# Peripheral.net
KiCad netlist of a schematic drawn in Altium Designer
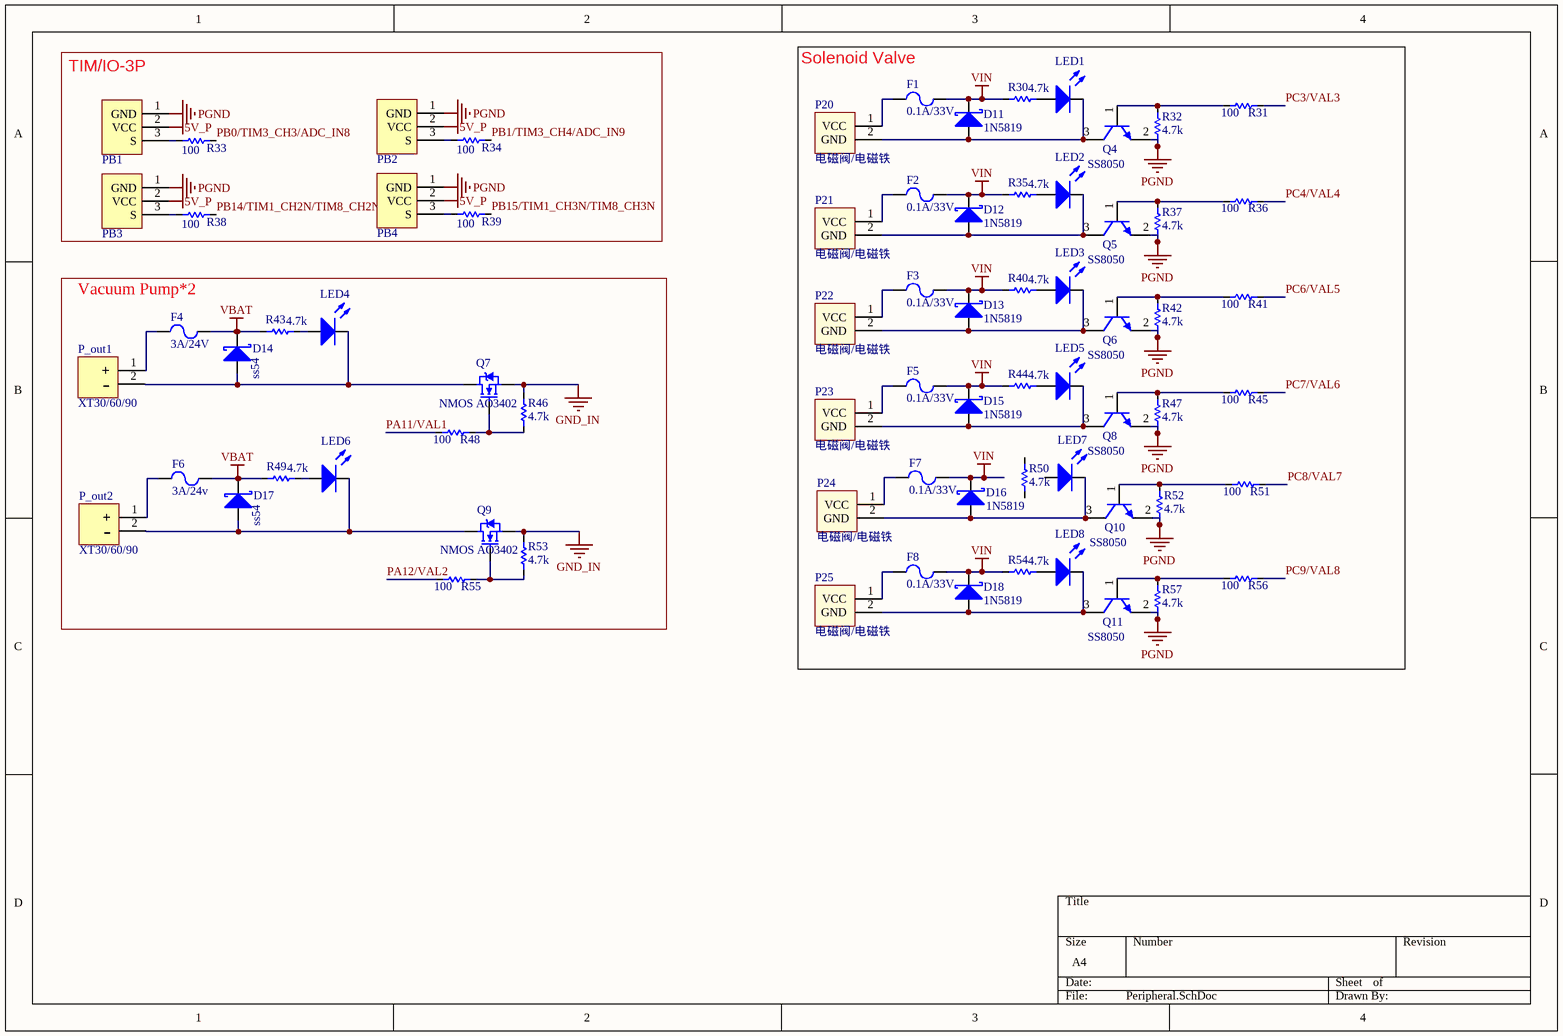
[diagram p0: Peripheral.SchDoc]

(export (version "E")
  (design (tool "Eeschema 10.0.6"))
  (components
    (comp (ref "D11")
      (value "1N5819")
      (footprint "SOD-323-")
      (description "Schottky Diode")
      (fields (field (name "PUBLISHER") "Altium Limited"))
      (libsource (lib "MyComponents_v2.5") (part "D Schottky"))
    )
    (comp (ref "D12")
      (value "1N5819")
      (footprint "SOD-323-")
      (description "Schottky Diode")
      (fields (field (name "PUBLISHER") "Altium Limited"))
      (libsource (lib "MyComponents_v2.5") (part "D Schottky"))
    )
    (comp (ref "D13")
      (value "1N5819")
      (footprint "SOD-323-")
      (description "Schottky Diode")
      (fields (field (name "PUBLISHER") "Altium Limited"))
      (libsource (lib "MyComponents_v2.5") (part "D Schottky"))
    )
    (comp (ref "D14")
      (value "ss54")
      (footprint "SMAF/DO-214AC")
      (description "Schottky Diode")
      (fields (field (name "PUBLISHER") "Altium Limited"))
      (libsource (lib "MyComponents_v2.5") (part "D Schottky_SOD323"))
    )
    (comp (ref "D15")
      (value "1N5819")
      (footprint "SOD-323-")
      (description "Schottky Diode")
      (fields (field (name "PUBLISHER") "Altium Limited"))
      (libsource (lib "MyComponents_v2.5") (part "D Schottky"))
    )
    (comp (ref "D16")
      (value "1N5819")
      (footprint "SOD-323-")
      (description "Schottky Diode")
      (fields (field (name "PUBLISHER") "Altium Limited"))
      (libsource (lib "MyComponents_v2.5") (part "D Schottky"))
    )
    (comp (ref "D17")
      (value "ss54")
      (footprint "SMAF/DO-214AC")
      (description "Schottky Diode")
      (fields (field (name "PUBLISHER") "Altium Limited"))
      (libsource (lib "MyComponents_v2.5") (part "D Schottky_SOD323"))
    )
    (comp (ref "D18")
      (value "1N5819")
      (footprint "SOD-323-")
      (description "Schottky Diode")
      (fields (field (name "PUBLISHER") "Altium Limited"))
      (libsource (lib "MyComponents_v2.5") (part "D Schottky"))
    )
    (comp (ref "F1")
      (value "0.1A/33V")
      (footprint "0603C")
      (description "0603自恢复保险丝")
      (libsource (lib "MyComponents_v2.5") (part "Finance"))
    )
    (comp (ref "F2")
      (value "0.1A/33V")
      (footprint "0603C")
      (description "0603自恢复保险丝")
      (libsource (lib "MyComponents_v2.5") (part "Finance"))
    )
    (comp (ref "F3")
      (value "0.1A/33V")
      (footprint "0603C")
      (description "0603自恢复保险丝")
      (libsource (lib "MyComponents_v2.5") (part "Finance"))
    )
    (comp (ref "F4")
      (value "3A/24V")
      (footprint "0603C")
      (description "0603自恢复保险丝")
      (libsource (lib "MyComponents_v2.5") (part "Finance"))
    )
    (comp (ref "F5")
      (value "0.1A/33V")
      (footprint "0603C")
      (description "0603自恢复保险丝")
      (libsource (lib "MyComponents_v2.5") (part "Finance"))
    )
    (comp (ref "F6")
      (value "3A/24v")
      (footprint "0603C")
      (description "0603自恢复保险丝")
      (libsource (lib "MyComponents_v2.5") (part "Finance"))
    )
    (comp (ref "F7")
      (value "0.1A/33V")
      (footprint "0603C")
      (description "0603自恢复保险丝")
      (libsource (lib "MyComponents_v2.5") (part "Finance"))
    )
    (comp (ref "F8")
      (value "0.1A/33V")
      (footprint "0603C")
      (description "0603自恢复保险丝")
      (libsource (lib "MyComponents_v2.5") (part "Finance"))
    )
    (comp (ref "LED1")
      (value "LED_RED")
      (footprint "0603LED_B")
      (description "Typical RED, GREEN, YELLOW, AMBER GaAs LED")
      (fields (field (name "PUBLISHER") "Altium Limited"))
      (libsource (lib "MyComponents_v2.5") (part "LED"))
    )
    (comp (ref "LED2")
      (value "LED_RED")
      (footprint "0603LED_B")
      (description "Typical RED, GREEN, YELLOW, AMBER GaAs LED")
      (fields (field (name "PUBLISHER") "Altium Limited"))
      (libsource (lib "MyComponents_v2.5") (part "LED"))
    )
    (comp (ref "LED3")
      (value "LED_RED")
      (footprint "0603LED_B")
      (description "Typical RED, GREEN, YELLOW, AMBER GaAs LED")
      (fields (field (name "PUBLISHER") "Altium Limited"))
      (libsource (lib "MyComponents_v2.5") (part "LED"))
    )
    (comp (ref "LED4")
      (value "LED_RED")
      (footprint "0603LED_B")
      (description "Typical RED, GREEN, YELLOW, AMBER GaAs LED")
      (fields (field (name "PUBLISHER") "Altium Limited"))
      (libsource (lib "MyComponents_v2.5") (part "LED"))
    )
    (comp (ref "LED5")
      (value "LED_RED")
      (footprint "0603LED_B")
      (description "Typical RED, GREEN, YELLOW, AMBER GaAs LED")
      (fields (field (name "PUBLISHER") "Altium Limited"))
      (libsource (lib "MyComponents_v2.5") (part "LED"))
    )
    (comp (ref "LED6")
      (value "LED_RED")
      (footprint "0603LED_B")
      (description "Typical RED, GREEN, YELLOW, AMBER GaAs LED")
      (fields (field (name "PUBLISHER") "Altium Limited"))
      (libsource (lib "MyComponents_v2.5") (part "LED"))
    )
    (comp (ref "LED7")
      (value "LED_RED")
      (footprint "0603LED_B")
      (description "Typical RED, GREEN, YELLOW, AMBER GaAs LED")
      (fields (field (name "PUBLISHER") "Altium Limited"))
      (libsource (lib "MyComponents_v2.5") (part "LED"))
    )
    (comp (ref "LED8")
      (value "LED_RED")
      (footprint "0603LED_B")
      (description "Typical RED, GREEN, YELLOW, AMBER GaAs LED")
      (fields (field (name "PUBLISHER") "Altium Limited"))
      (libsource (lib "MyComponents_v2.5") (part "LED"))
    )
    (comp (ref "P20")
      (value "电磁阀/电磁铁")
      (footprint "HY2.00MM 2X1_立式")
      (libsource (lib "MyComponents_v2.5") (part "电磁阀/电磁铁"))
    )
    (comp (ref "P21")
      (value "电磁阀/电磁铁")
      (footprint "HY2.00MM 2X1_立式")
      (libsource (lib "MyComponents_v2.5") (part "电磁阀/电磁铁"))
    )
    (comp (ref "P22")
      (value "电磁阀/电磁铁")
      (footprint "HY2.00MM 2X1_立式")
      (libsource (lib "MyComponents_v2.5") (part "电磁阀/电磁铁"))
    )
    (comp (ref "P23")
      (value "电磁阀/电磁铁")
      (footprint "HY2.00MM 2X1_立式")
      (libsource (lib "MyComponents_v2.5") (part "电磁阀/电磁铁"))
    )
    (comp (ref "P24")
      (value "电磁阀/电磁铁")
      (footprint "HY2.00MM 2X1_立式")
      (libsource (lib "MyComponents_v2.5") (part "电磁阀/电磁铁"))
    )
    (comp (ref "P25")
      (value "电磁阀/电磁铁")
      (footprint "HY2.00MM 2X1_立式")
      (libsource (lib "MyComponents_v2.5") (part "电磁阀/电磁铁"))
    )
    (comp (ref "PB1")
      (value "3Pin_IO")
      (footprint "HY2.00MM 3x1立式")
      (description "3pin input/output. V+S+G")
      (libsource (lib "MyComponents_v2.5") (part "3Pin_IO"))
    )
    (comp (ref "PB2")
      (value "3Pin_IO")
      (footprint "HY2.00MM 3x1立式")
      (description "3pin input/output. V+S+G")
      (libsource (lib "MyComponents_v2.5") (part "3Pin_IO"))
    )
    (comp (ref "PB3")
      (value "3Pin_IO")
      (footprint "HY2.00MM 3x1立式")
      (description "3pin input/output. V+S+G")
      (libsource (lib "MyComponents_v2.5") (part "3Pin_IO"))
    )
    (comp (ref "PB4")
      (value "3Pin_IO")
      (footprint "HY2.00MM 3x1立式")
      (description "3pin input/output. V+S+G")
      (libsource (lib "MyComponents_v2.5") (part "3Pin_IO"))
    )
    (comp (ref "P_out1")
      (value "XT30/60/90")
      (footprint "XT30UPB-FEMALE")
      (libsource (lib "MyComponents_v2.5") (part "XT30/60/90"))
    )
    (comp (ref "P_out2")
      (value "XT30/60/90")
      (footprint "XT30UPB-FEMALE")
      (libsource (lib "MyComponents_v2.5") (part "XT30/60/90"))
    )
    (comp (ref "Q4")
      (value "SS8050")
      (footprint "SOT-23-3")
      (description "NPN Bipolar Transistor")
      (fields (field (name "PUBLISHER") "Altium Limited"))
      (libsource (lib "MyComponents_v2.5") (part "NPN"))
    )
    (comp (ref "Q5")
      (value "SS8050")
      (footprint "SOT-23-3")
      (description "NPN Bipolar Transistor")
      (fields (field (name "PUBLISHER") "Altium Limited"))
      (libsource (lib "MyComponents_v2.5") (part "NPN"))
    )
    (comp (ref "Q6")
      (value "SS8050")
      (footprint "SOT-23-3")
      (description "NPN Bipolar Transistor")
      (fields (field (name "PUBLISHER") "Altium Limited"))
      (libsource (lib "MyComponents_v2.5") (part "NPN"))
    )
    (comp (ref "Q7")
      (value "NMOS AO3402")
      (footprint "SOT-23-3")
      (description "N-Channel Power MOSFET")
      (fields (field (name "PUBLISHER") "Altium Limited"))
      (libsource (lib "MyComponents_v2.5") (part "NMOS(SOT23)"))
    )
    (comp (ref "Q8")
      (value "SS8050")
      (footprint "SOT-23-3")
      (description "NPN Bipolar Transistor")
      (fields (field (name "PUBLISHER") "Altium Limited"))
      (libsource (lib "MyComponents_v2.5") (part "NPN"))
    )
    (comp (ref "Q9")
      (value "NMOS AO3402")
      (footprint "SOT-23-3")
      (description "N-Channel Power MOSFET")
      (fields (field (name "PUBLISHER") "Altium Limited"))
      (libsource (lib "MyComponents_v2.5") (part "NMOS(SOT23)"))
    )
    (comp (ref "Q10")
      (value "SS8050")
      (footprint "SOT-23-3")
      (description "NPN Bipolar Transistor")
      (fields (field (name "PUBLISHER") "Altium Limited"))
      (libsource (lib "MyComponents_v2.5") (part "NPN"))
    )
    (comp (ref "Q11")
      (value "SS8050")
      (footprint "SOT-23-3")
      (description "NPN Bipolar Transistor")
      (fields (field (name "PUBLISHER") "Altium Limited"))
      (libsource (lib "MyComponents_v2.5") (part "NPN"))
    )
    (comp (ref "R30")
      (value "4.7k")
      (footprint "0603R")
      (description "Resistor")
      (fields (field (name "PUBLISHER") "Altium Limited"))
      (libsource (lib "MyComponents_v2.5") (part "Res1"))
    )
    (comp (ref "R31")
      (value "100")
      (footprint "0603R")
      (description "Resistor")
      (fields (field (name "PUBLISHER") "Altium Limited"))
      (libsource (lib "MyComponents_v2.5") (part "Res1"))
    )
    (comp (ref "R32")
      (value "4.7k")
      (footprint "0603R")
      (description "Resistor")
      (fields (field (name "PUBLISHER") "Altium Limited"))
      (libsource (lib "MyComponents_v2.4") (part "Res1"))
    )
    (comp (ref "R33")
      (value "100")
      (footprint "0603R")
      (description "Resistor")
      (fields (field (name "PUBLISHER") "Altium Limited"))
      (libsource (lib "MyComponents_v2.5") (part "Res1"))
    )
    (comp (ref "R34")
      (value "100")
      (footprint "0603R")
      (description "Resistor")
      (fields (field (name "PUBLISHER") "Altium Limited"))
      (libsource (lib "MyComponents_v2.5") (part "Res1"))
    )
    (comp (ref "R35")
      (value "4.7k")
      (footprint "0603R")
      (description "Resistor")
      (fields (field (name "PUBLISHER") "Altium Limited"))
      (libsource (lib "MyComponents_v2.5") (part "Res1"))
    )
    (comp (ref "R36")
      (value "100")
      (footprint "0603R")
      (description "Resistor")
      (fields (field (name "PUBLISHER") "Altium Limited"))
      (libsource (lib "MyComponents_v2.5") (part "Res1"))
    )
    (comp (ref "R37")
      (value "4.7k")
      (footprint "0603R")
      (description "Resistor")
      (fields (field (name "PUBLISHER") "Altium Limited"))
      (libsource (lib "MyComponents_v2.4") (part "Res1"))
    )
    (comp (ref "R38")
      (value "100")
      (footprint "0603R")
      (description "Resistor")
      (fields (field (name "PUBLISHER") "Altium Limited"))
      (libsource (lib "MyComponents_v2.5") (part "Res1"))
    )
    (comp (ref "R39")
      (value "100")
      (footprint "0603R")
      (description "Resistor")
      (fields (field (name "PUBLISHER") "Altium Limited"))
      (libsource (lib "MyComponents_v2.5") (part "Res1"))
    )
    (comp (ref "R40")
      (value "4.7k")
      (footprint "0603R")
      (description "Resistor")
      (fields (field (name "PUBLISHER") "Altium Limited"))
      (libsource (lib "MyComponents_v2.5") (part "Res1"))
    )
    (comp (ref "R41")
      (value "100")
      (footprint "0603R")
      (description "Resistor")
      (fields (field (name "PUBLISHER") "Altium Limited"))
      (libsource (lib "MyComponents_v2.5") (part "Res1"))
    )
    (comp (ref "R42")
      (value "4.7k")
      (footprint "0603R")
      (description "Resistor")
      (fields (field (name "PUBLISHER") "Altium Limited"))
      (libsource (lib "MyComponents_v2.4") (part "Res1"))
    )
    (comp (ref "R43")
      (value "4.7k")
      (footprint "0603R")
      (description "Resistor")
      (fields (field (name "PUBLISHER") "Altium Limited"))
      (libsource (lib "MyComponents_v2.5") (part "Res1"))
    )
    (comp (ref "R44")
      (value "4.7k")
      (footprint "0603R")
      (description "Resistor")
      (fields (field (name "PUBLISHER") "Altium Limited"))
      (libsource (lib "MyComponents_v2.5") (part "Res1"))
    )
    (comp (ref "R45")
      (value "100")
      (footprint "0603R")
      (description "Resistor")
      (fields (field (name "PUBLISHER") "Altium Limited"))
      (libsource (lib "MyComponents_v2.5") (part "Res1"))
    )
    (comp (ref "R46")
      (value "4.7k")
      (footprint "0603R")
      (description "Resistor")
      (fields (field (name "PUBLISHER") "Altium Limited"))
      (libsource (lib "MyComponents_v2.4") (part "Res1"))
    )
    (comp (ref "R47")
      (value "4.7k")
      (footprint "0603R")
      (description "Resistor")
      (fields (field (name "PUBLISHER") "Altium Limited"))
      (libsource (lib "MyComponents_v2.4") (part "Res1"))
    )
    (comp (ref "R48")
      (value "100")
      (footprint "0603R")
      (description "Resistor")
      (fields (field (name "PUBLISHER") "Altium Limited"))
      (libsource (lib "MyComponents_v2.5") (part "Res1"))
    )
    (comp (ref "R49")
      (value "4.7k")
      (footprint "0603R")
      (description "Resistor")
      (fields (field (name "PUBLISHER") "Altium Limited"))
      (libsource (lib "MyComponents_v2.5") (part "Res1"))
    )
    (comp (ref "R50")
      (value "4.7k")
      (footprint "0603R")
      (description "Resistor")
      (fields (field (name "PUBLISHER") "Altium Limited"))
      (libsource (lib "MyComponents_v2.5") (part "Res1"))
    )
    (comp (ref "R51")
      (value "100")
      (footprint "0603R")
      (description "Resistor")
      (fields (field (name "PUBLISHER") "Altium Limited"))
      (libsource (lib "MyComponents_v2.5") (part "Res1"))
    )
    (comp (ref "R52")
      (value "4.7k")
      (footprint "0603R")
      (description "Resistor")
      (fields (field (name "PUBLISHER") "Altium Limited"))
      (libsource (lib "MyComponents_v2.4") (part "Res1"))
    )
    (comp (ref "R53")
      (value "4.7k")
      (footprint "0603R")
      (description "Resistor")
      (fields (field (name "PUBLISHER") "Altium Limited"))
      (libsource (lib "MyComponents_v2.4") (part "Res1"))
    )
    (comp (ref "R54")
      (value "4.7k")
      (footprint "0603R")
      (description "Resistor")
      (fields (field (name "PUBLISHER") "Altium Limited"))
      (libsource (lib "MyComponents_v2.5") (part "Res1"))
    )
    (comp (ref "R55")
      (value "100")
      (footprint "0603R")
      (description "Resistor")
      (fields (field (name "PUBLISHER") "Altium Limited"))
      (libsource (lib "MyComponents_v2.5") (part "Res1"))
    )
    (comp (ref "R56")
      (value "100")
      (footprint "0603R")
      (description "Resistor")
      (fields (field (name "PUBLISHER") "Altium Limited"))
      (libsource (lib "MyComponents_v2.5") (part "Res1"))
    )
    (comp (ref "R57")
      (value "4.7k")
      (footprint "0603R")
      (description "Resistor")
      (fields (field (name "PUBLISHER") "Altium Limited"))
      (libsource (lib "MyComponents_v2.4") (part "Res1"))
    )
  )
  (nets
    (net (code "1") (name "/PA11{slash}VAL1") (class "Default")
      (node (ref "R48") (pin "1") (pinfunction "1_1") (pintype "passive"))
    )
    (net (code "2") (name "/PA12{slash}VAL2") (class "Default")
      (node (ref "R55") (pin "1") (pinfunction "1_1") (pintype "passive"))
    )
    (net (code "3") (name "/PB0{slash}TIM3_CH3{slash}ADC_IN8") (class "Default")
      (node (ref "R33") (pin "2") (pinfunction "2_2") (pintype "passive"))
    )
    (net (code "4") (name "/PB1{slash}TIM3_CH4{slash}ADC_IN9") (class "Default")
      (node (ref "R34") (pin "2") (pinfunction "2_2") (pintype "passive"))
    )
    (net (code "5") (name "/PB14{slash}TIM1_CH2N{slash}TIM8_CH2N") (class "Default")
      (node (ref "R38") (pin "2") (pinfunction "2_2") (pintype "passive"))
    )
    (net (code "6") (name "/PB15{slash}TIM1_CH3N{slash}TIM8_CH3N") (class "Default")
      (node (ref "R39") (pin "2") (pinfunction "2_2") (pintype "passive"))
    )
    (net (code "7") (name "/PC3{slash}VAL3") (class "Default")
      (node (ref "R31") (pin "2") (pinfunction "2_2") (pintype "passive"))
    )
    (net (code "8") (name "/PC4{slash}VAL4") (class "Default")
      (node (ref "R36") (pin "2") (pinfunction "2_2") (pintype "passive"))
    )
    (net (code "9") (name "/PC6{slash}VAL5") (class "Default")
      (node (ref "R41") (pin "2") (pinfunction "2_2") (pintype "passive"))
    )
    (net (code "10") (name "/PC7{slash}VAL6") (class "Default")
      (node (ref "R45") (pin "2") (pinfunction "2_2") (pintype "passive"))
    )
    (net (code "11") (name "/PC8{slash}VAL7") (class "Default")
      (node (ref "R51") (pin "2") (pinfunction "2_2") (pintype "passive"))
    )
    (net (code "12") (name "/PC9{slash}VAL8") (class "Default")
      (node (ref "R56") (pin "2") (pinfunction "2_2") (pintype "passive"))
    )
    (net (code "13") (name "5V_P") (class "Default")
      (node (ref "PB1") (pin "2") (pinfunction "VCC_2") (pintype "passive"))
      (node (ref "PB2") (pin "2") (pinfunction "VCC_2") (pintype "passive"))
      (node (ref "PB3") (pin "2") (pinfunction "VCC_2") (pintype "passive"))
      (node (ref "PB4") (pin "2") (pinfunction "VCC_2") (pintype "passive"))
    )
    (net (code "14") (name "GND_IN") (class "Default")
      (node (ref "Q7") (pin "2") (pinfunction "S_2") (pintype "passive"))
      (node (ref "Q9") (pin "2") (pinfunction "S_2") (pintype "passive"))
      (node (ref "R46") (pin "2") (pinfunction "2_2") (pintype "passive"))
      (node (ref "R53") (pin "2") (pinfunction "2_2") (pintype "passive"))
    )
    (net (code "15") (name "Net-(LED1-Pad1)") (class "Default")
      (node (ref "LED1") (pin "1") (pinfunction "1_1") (pintype "passive"))
      (node (ref "R30") (pin "2") (pinfunction "2_2") (pintype "passive"))
    )
    (net (code "16") (name "Net-(LED2-Pad1)") (class "Default")
      (node (ref "LED2") (pin "1") (pinfunction "1_1") (pintype "passive"))
      (node (ref "R35") (pin "2") (pinfunction "2_2") (pintype "passive"))
    )
    (net (code "17") (name "Net-(LED3-Pad1)") (class "Default")
      (node (ref "LED3") (pin "1") (pinfunction "1_1") (pintype "passive"))
      (node (ref "R40") (pin "2") (pinfunction "2_2") (pintype "passive"))
    )
    (net (code "18") (name "Net-(LED4-Pad1)") (class "Default")
      (node (ref "LED4") (pin "1") (pinfunction "1_1") (pintype "passive"))
      (node (ref "R43") (pin "2") (pinfunction "2_2") (pintype "passive"))
    )
    (net (code "19") (name "Net-(LED5-Pad1)") (class "Default")
      (node (ref "LED5") (pin "1") (pinfunction "1_1") (pintype "passive"))
      (node (ref "R44") (pin "2") (pinfunction "2_2") (pintype "passive"))
    )
    (net (code "20") (name "Net-(LED6-Pad1)") (class "Default")
      (node (ref "LED6") (pin "1") (pinfunction "1_1") (pintype "passive"))
      (node (ref "R49") (pin "2") (pinfunction "2_2") (pintype "passive"))
    )
    (net (code "21") (name "Net-(LED8-Pad1)") (class "Default")
      (node (ref "LED8") (pin "1") (pinfunction "1_1") (pintype "passive"))
      (node (ref "R54") (pin "2") (pinfunction "2_2") (pintype "passive"))
    )
    (net (code "22") (name "Net-(P20-GND)") (class "Default")
      (node (ref "D11") (pin "1") (pinfunction "1_1") (pintype "passive"))
      (node (ref "LED1") (pin "2") (pinfunction "2_2") (pintype "passive"))
      (node (ref "P20") (pin "2") (pinfunction "GND_2") (pintype "passive"))
      (node (ref "Q4") (pin "3") (pinfunction "C_3") (pintype "passive"))
    )
    (net (code "23") (name "Net-(P20-VCC)") (class "Default")
      (node (ref "F1") (pin "1") (pinfunction "1_1") (pintype "passive"))
      (node (ref "P20") (pin "1") (pinfunction "VCC_1") (pintype "passive"))
    )
    (net (code "24") (name "Net-(P21-GND)") (class "Default")
      (node (ref "D12") (pin "1") (pinfunction "1_1") (pintype "passive"))
      (node (ref "LED2") (pin "2") (pinfunction "2_2") (pintype "passive"))
      (node (ref "P21") (pin "2") (pinfunction "GND_2") (pintype "passive"))
      (node (ref "Q5") (pin "3") (pinfunction "C_3") (pintype "passive"))
    )
    (net (code "25") (name "Net-(P21-VCC)") (class "Default")
      (node (ref "F2") (pin "1") (pinfunction "1_1") (pintype "passive"))
      (node (ref "P21") (pin "1") (pinfunction "VCC_1") (pintype "passive"))
    )
    (net (code "26") (name "Net-(P22-GND)") (class "Default")
      (node (ref "D13") (pin "1") (pinfunction "1_1") (pintype "passive"))
      (node (ref "LED3") (pin "2") (pinfunction "2_2") (pintype "passive"))
      (node (ref "P22") (pin "2") (pinfunction "GND_2") (pintype "passive"))
      (node (ref "Q6") (pin "3") (pinfunction "C_3") (pintype "passive"))
    )
    (net (code "27") (name "Net-(P22-VCC)") (class "Default")
      (node (ref "F3") (pin "1") (pinfunction "1_1") (pintype "passive"))
      (node (ref "P22") (pin "1") (pinfunction "VCC_1") (pintype "passive"))
    )
    (net (code "28") (name "Net-(P23-GND)") (class "Default")
      (node (ref "D15") (pin "1") (pinfunction "1_1") (pintype "passive"))
      (node (ref "LED5") (pin "2") (pinfunction "2_2") (pintype "passive"))
      (node (ref "P23") (pin "2") (pinfunction "GND_2") (pintype "passive"))
      (node (ref "Q8") (pin "3") (pinfunction "C_3") (pintype "passive"))
    )
    (net (code "29") (name "Net-(P23-VCC)") (class "Default")
      (node (ref "F5") (pin "1") (pinfunction "1_1") (pintype "passive"))
      (node (ref "P23") (pin "1") (pinfunction "VCC_1") (pintype "passive"))
    )
    (net (code "30") (name "Net-(P24-GND)") (class "Default")
      (node (ref "D16") (pin "1") (pinfunction "1_1") (pintype "passive"))
      (node (ref "LED7") (pin "2") (pinfunction "2_2") (pintype "passive"))
      (node (ref "P24") (pin "2") (pinfunction "GND_2") (pintype "passive"))
      (node (ref "Q10") (pin "3") (pinfunction "C_3") (pintype "passive"))
    )
    (net (code "31") (name "Net-(P24-VCC)") (class "Default")
      (node (ref "F7") (pin "1") (pinfunction "1_1") (pintype "passive"))
      (node (ref "P24") (pin "1") (pinfunction "VCC_1") (pintype "passive"))
    )
    (net (code "32") (name "Net-(P25-GND)") (class "Default")
      (node (ref "D18") (pin "1") (pinfunction "1_1") (pintype "passive"))
      (node (ref "LED8") (pin "2") (pinfunction "2_2") (pintype "passive"))
      (node (ref "P25") (pin "2") (pinfunction "GND_2") (pintype "passive"))
      (node (ref "Q11") (pin "3") (pinfunction "C_3") (pintype "passive"))
    )
    (net (code "33") (name "Net-(P25-VCC)") (class "Default")
      (node (ref "F8") (pin "1") (pinfunction "1_1") (pintype "passive"))
      (node (ref "P25") (pin "1") (pinfunction "VCC_1") (pintype "passive"))
    )
    (net (code "34") (name "Net-(PB1-S)") (class "Default")
      (node (ref "PB1") (pin "3") (pinfunction "S_3") (pintype "passive"))
      (node (ref "R33") (pin "1") (pinfunction "1_1") (pintype "passive"))
    )
    (net (code "35") (name "Net-(PB2-S)") (class "Default")
      (node (ref "PB2") (pin "3") (pinfunction "S_3") (pintype "passive"))
      (node (ref "R34") (pin "1") (pinfunction "1_1") (pintype "passive"))
    )
    (net (code "36") (name "Net-(PB3-S)") (class "Default")
      (node (ref "PB3") (pin "3") (pinfunction "S_3") (pintype "passive"))
      (node (ref "R38") (pin "1") (pinfunction "1_1") (pintype "passive"))
    )
    (net (code "37") (name "Net-(PB4-S)") (class "Default")
      (node (ref "PB4") (pin "3") (pinfunction "S_3") (pintype "passive"))
      (node (ref "R39") (pin "1") (pinfunction "1_1") (pintype "passive"))
    )
    (net (code "38") (name "Net-(P_out1-+)") (class "Default")
      (node (ref "F4") (pin "1") (pinfunction "1_1") (pintype "passive"))
      (node (ref "P_out1") (pin "1") (pinfunction "+_1") (pintype "passive"))
    )
    (net (code "39") (name "Net-(P_out1--)") (class "Default")
      (node (ref "D14") (pin "1") (pinfunction "1_1") (pintype "passive"))
      (node (ref "LED4") (pin "2") (pinfunction "2_2") (pintype "passive"))
      (node (ref "P_out1") (pin "2") (pinfunction "-_2") (pintype "passive"))
      (node (ref "Q7") (pin "3") (pinfunction "D_3") (pintype "passive"))
    )
    (net (code "40") (name "Net-(P_out2-+)") (class "Default")
      (node (ref "F6") (pin "1") (pinfunction "1_1") (pintype "passive"))
      (node (ref "P_out2") (pin "1") (pinfunction "+_1") (pintype "passive"))
    )
    (net (code "41") (name "Net-(P_out2--)") (class "Default")
      (node (ref "D17") (pin "1") (pinfunction "1_1") (pintype "passive"))
      (node (ref "LED6") (pin "2") (pinfunction "2_2") (pintype "passive"))
      (node (ref "P_out2") (pin "2") (pinfunction "-_2") (pintype "passive"))
      (node (ref "Q9") (pin "3") (pinfunction "D_3") (pintype "passive"))
    )
    (net (code "42") (name "Net-(Q4-B)") (class "Default")
      (node (ref "Q4") (pin "1") (pinfunction "B_1") (pintype "passive"))
      (node (ref "R31") (pin "1") (pinfunction "1_1") (pintype "passive"))
      (node (ref "R32") (pin "2") (pinfunction "2_2") (pintype "passive"))
    )
    (net (code "43") (name "Net-(Q5-B)") (class "Default")
      (node (ref "Q5") (pin "1") (pinfunction "B_1") (pintype "passive"))
      (node (ref "R36") (pin "1") (pinfunction "1_1") (pintype "passive"))
      (node (ref "R37") (pin "2") (pinfunction "2_2") (pintype "passive"))
    )
    (net (code "44") (name "Net-(Q6-B)") (class "Default")
      (node (ref "Q6") (pin "1") (pinfunction "B_1") (pintype "passive"))
      (node (ref "R41") (pin "1") (pinfunction "1_1") (pintype "passive"))
      (node (ref "R42") (pin "2") (pinfunction "2_2") (pintype "passive"))
    )
    (net (code "45") (name "Net-(Q7-G)") (class "Default")
      (node (ref "Q7") (pin "1") (pinfunction "G_1") (pintype "passive"))
      (node (ref "R46") (pin "1") (pinfunction "1_1") (pintype "passive"))
      (node (ref "R48") (pin "2") (pinfunction "2_2") (pintype "passive"))
    )
    (net (code "46") (name "Net-(Q8-B)") (class "Default")
      (node (ref "Q8") (pin "1") (pinfunction "B_1") (pintype "passive"))
      (node (ref "R45") (pin "1") (pinfunction "1_1") (pintype "passive"))
      (node (ref "R47") (pin "2") (pinfunction "2_2") (pintype "passive"))
    )
    (net (code "47") (name "Net-(Q9-G)") (class "Default")
      (node (ref "Q9") (pin "1") (pinfunction "G_1") (pintype "passive"))
      (node (ref "R53") (pin "1") (pinfunction "1_1") (pintype "passive"))
      (node (ref "R55") (pin "2") (pinfunction "2_2") (pintype "passive"))
    )
    (net (code "48") (name "Net-(Q10-B)") (class "Default")
      (node (ref "Q10") (pin "1") (pinfunction "B_1") (pintype "passive"))
      (node (ref "R51") (pin "1") (pinfunction "1_1") (pintype "passive"))
      (node (ref "R52") (pin "2") (pinfunction "2_2") (pintype "passive"))
    )
    (net (code "49") (name "Net-(Q11-B)") (class "Default")
      (node (ref "Q11") (pin "1") (pinfunction "B_1") (pintype "passive"))
      (node (ref "R56") (pin "1") (pinfunction "1_1") (pintype "passive"))
      (node (ref "R57") (pin "2") (pinfunction "2_2") (pintype "passive"))
    )
    (net (code "50") (name "PGND") (class "Default")
      (node (ref "PB1") (pin "1") (pinfunction "GND_1") (pintype "passive"))
      (node (ref "PB2") (pin "1") (pinfunction "GND_1") (pintype "passive"))
      (node (ref "PB3") (pin "1") (pinfunction "GND_1") (pintype "passive"))
      (node (ref "PB4") (pin "1") (pinfunction "GND_1") (pintype "passive"))
      (node (ref "Q10") (pin "2") (pinfunction "E_2") (pintype "passive"))
      (node (ref "Q11") (pin "2") (pinfunction "E_2") (pintype "passive"))
      (node (ref "Q4") (pin "2") (pinfunction "E_2") (pintype "passive"))
      (node (ref "Q5") (pin "2") (pinfunction "E_2") (pintype "passive"))
      (node (ref "Q6") (pin "2") (pinfunction "E_2") (pintype "passive"))
      (node (ref "Q8") (pin "2") (pinfunction "E_2") (pintype "passive"))
      (node (ref "R32") (pin "1") (pinfunction "1_1") (pintype "passive"))
      (node (ref "R37") (pin "1") (pinfunction "1_1") (pintype "passive"))
      (node (ref "R42") (pin "1") (pinfunction "1_1") (pintype "passive"))
      (node (ref "R47") (pin "1") (pinfunction "1_1") (pintype "passive"))
      (node (ref "R52") (pin "1") (pinfunction "1_1") (pintype "passive"))
      (node (ref "R57") (pin "1") (pinfunction "1_1") (pintype "passive"))
    )
    (net (code "51") (name "VBAT") (class "Default")
      (node (ref "D14") (pin "2") (pinfunction "2_2") (pintype "passive"))
      (node (ref "D17") (pin "2") (pinfunction "2_2") (pintype "passive"))
      (node (ref "F4") (pin "2") (pinfunction "2_2") (pintype "passive"))
      (node (ref "F6") (pin "2") (pinfunction "2_2") (pintype "passive"))
      (node (ref "R43") (pin "1") (pinfunction "1_1") (pintype "passive"))
      (node (ref "R49") (pin "1") (pinfunction "1_1") (pintype "passive"))
    )
    (net (code "52") (name "VIN") (class "Default")
      (node (ref "D11") (pin "2") (pinfunction "2_2") (pintype "passive"))
      (node (ref "D12") (pin "2") (pinfunction "2_2") (pintype "passive"))
      (node (ref "D13") (pin "2") (pinfunction "2_2") (pintype "passive"))
      (node (ref "D15") (pin "2") (pinfunction "2_2") (pintype "passive"))
      (node (ref "D16") (pin "2") (pinfunction "2_2") (pintype "passive"))
      (node (ref "D18") (pin "2") (pinfunction "2_2") (pintype "passive"))
      (node (ref "F1") (pin "2") (pinfunction "2_2") (pintype "passive"))
      (node (ref "F2") (pin "2") (pinfunction "2_2") (pintype "passive"))
      (node (ref "F3") (pin "2") (pinfunction "2_2") (pintype "passive"))
      (node (ref "F5") (pin "2") (pinfunction "2_2") (pintype "passive"))
      (node (ref "F7") (pin "2") (pinfunction "2_2") (pintype "passive"))
      (node (ref "F8") (pin "2") (pinfunction "2_2") (pintype "passive"))
      (node (ref "R30") (pin "1") (pinfunction "1_1") (pintype "passive"))
      (node (ref "R35") (pin "1") (pinfunction "1_1") (pintype "passive"))
      (node (ref "R40") (pin "1") (pinfunction "1_1") (pintype "passive"))
      (node (ref "R44") (pin "1") (pinfunction "1_1") (pintype "passive"))
      (node (ref "R54") (pin "1") (pinfunction "1_1") (pintype "passive"))
    )
    (net (code "53") (name "unconnected-(LED7-Pad1)") (class "Default")
      (node (ref "LED7") (pin "1") (pinfunction "1_1") (pintype "passive"))
    )
    (net (code "54") (name "unconnected-(R50-Pad1)") (class "Default")
      (node (ref "R50") (pin "1") (pinfunction "1_1") (pintype "passive"))
    )
    (net (code "55") (name "unconnected-(R50-Pad2)") (class "Default")
      (node (ref "R50") (pin "2") (pinfunction "2_2") (pintype "passive"))
    )
  )
)
